# Power.net
KiCad netlist of a schematic drawn in Altium Designer
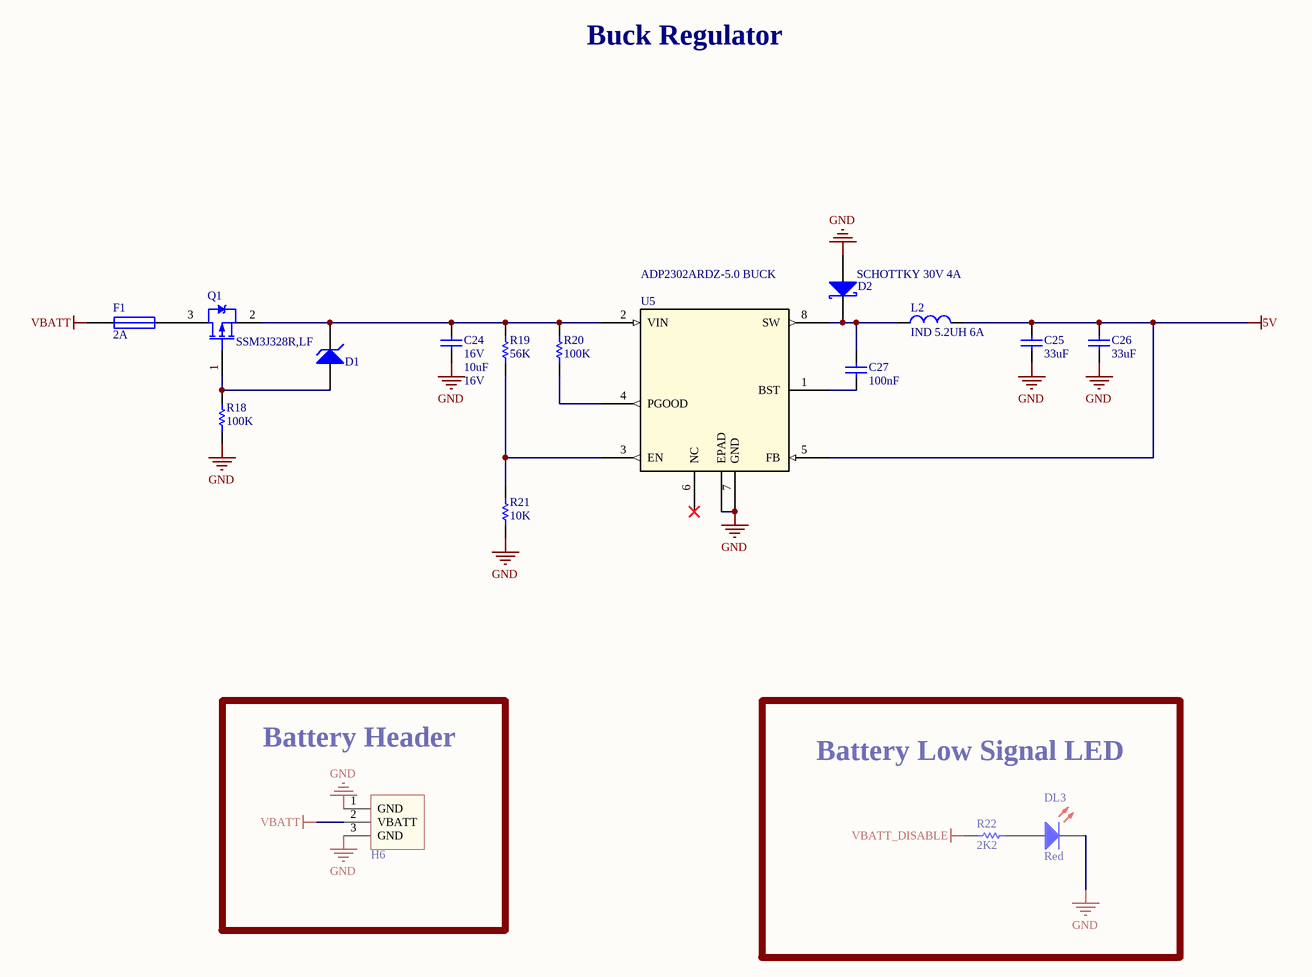
[diagram p0: Power.SchDoc]

(export (version "E")
  (design (tool "Eeschema 10.0.6"))
  (components
    (comp (ref "C24")
      (value "10uF")
      (footprint "CAPC2012L")
      (description "CAP CER 10uF X5R 16V 0805")
      (fields
        (field (name "MANUFACTURER") "Samsung Electro-Mechanics")
        (field (name "MANUFACTURER PART NUMBER") "CL21A106KOQNNWE")
        (field (name "VOLTAGE - RATED") "16V")
        (field (name "MAX VOLTAGE") "16V")
      )
      (libsource (lib "ENCE461AD19_19V2") (part "CC_10uF_16V_0805"))
    )
    (comp (ref "C25")
      (value "33uF")
      (footprint "CAPC2012L")
      (description "CAP CER 33uF X5R 6V3 0805")
      (fields
        (field (name "MANUFACTURER") "TDK Corporation")
        (field (name "MANUFACTURER PART NUMBER") "C2012X5R0J336M125AC")
      )
      (libsource (lib "ENCE461AD19_19V2") (part "CC_33uF_6V3_0805"))
    )
    (comp (ref "C26")
      (value "33uF")
      (footprint "CAPC2012L")
      (description "CAP CER 33uF X5R 6V3 0805")
      (fields
        (field (name "MANUFACTURER") "TDK Corporation")
        (field (name "MANUFACTURER PART NUMBER") "C2012X5R0J336M125AC")
      )
      (libsource (lib "ENCE461AD19_19V2") (part "CC_33uF_6V3_0805"))
    )
    (comp (ref "C27")
      (value "100nF")
      (footprint "CAPC1608L")
      (description "CAP CER 100nF X7R +-10% 50V 0603")
      (libsource (lib "ECE AD19Components_19V1") (part "CC_100nF_0603"))
    )
    (comp (ref "D1")
      (value "DIODE ZENER 5.6V")
      (footprint "DO-214AA_SCL")
      (description "DIODE ZENER 5.6V 5W DO214AA")
      (fields
        (field (name "MANUFACTURER") "Micro Commercial Co")
        (field (name "MANUFACTURER PART NUMBER") "SMBJ5339B-TP")
      )
      (libsource (lib "ENCE461AD19_19V2") (part "SMBJ5339B-TP"))
    )
    (comp (ref "D2")
      (value "SCHOTTKY 30V 4A")
      (footprint "SMC")
      (description "DIODE SCHOTTKY 30V 4A SMC")
      (fields
        (field (name "MANUFACTURER") "ON Semiconductor")
        (field (name "MANUFACTURER PART NUMBER") "MBRS330T3G")
      )
      (libsource (lib "ENCE461AD19_19V2") (part "MBRS330T3G"))
    )
    (comp (ref "DL3")
      (value "Red")
      (footprint "WL-SMCW0603")
      (description "LED Red 250mcd 0603 SMD")
      (fields
        (field (name "MANUFACTURER") "WURTH ELEKTRONIK")
        (field (name "MANUFACTURER PART NUMBER") "150060RS75000")
        (field (name "LED COLOUR") "Red")
      )
      (libsource (lib "ECE AD19Components_19V1") (part "DL_150060RS75000"))
    )
    (comp (ref "F1")
      (value "2A")
      (footprint "RESC3216N")
      (description "Fuse 2.0A Very Fast Acting 1206 SMD")
      (fields
        (field (name "MANUFACTURER") "MULTICOMP")
        (field (name "MANUFACTURER PART NUMBER") "MC12CF 002")
      )
      (libsource (lib "ECE AD19Components_19V1") (part "FS_Fuse_2.0A"))
    )
    (comp (ref "H6")
      (value "Battery_HEADER_3pin")
      (footprint "BATT_HEADER_3POS")
      (description "3Pin Header 2.54mm spacing")
      (libsource (lib "ENCE461AD19_19V2") (part "Battery_HEADER_3pin"))
    )
    (comp (ref "L2")
      (value "IND 5.2UH 6A")
      (footprint "INDUCTOR5u2")
      (description "FIXED IND 5.2UH 6A 22 MOHM SMD")
      (fields
        (field (name "MANUFACTURER") "Sumida America Components Inc.")
        (field (name "MANUFACTURER PART NUMBER") "CDRH104RNP-5R2NC")
      )
      (libsource (lib "ENCE461AD19_19V2") (part "CDRH104RNP-5R2NC"))
    )
    (comp (ref "Q1")
      (value "SSM3J328R,LF")
      (footprint "SOT23_L")
      (description "MOSFET P-CH 20V 6A SOT23-3")
      (fields
        (field (name "MANUFACTURER") "Toshiba")
        (field (name "MANUFACTURER PART NUMBER") "SSM3J328R,LF")
      )
      (libsource (lib "ECE AD19Components_19V1") (part "TM_SSM3J328R"))
    )
    (comp (ref "R18")
      (value "100K")
      (footprint "RESC1608L")
      (description "RES 100K OHM 1/10W 5% 0603 SMD")
      (libsource (lib "ECE AD19Components_19V1") (part "RS_100K"))
    )
    (comp (ref "R19")
      (value "56K")
      (footprint "RESC1608L")
      (description "RES 56.0K OHM 1/10W 5% 0603 SMD")
      (libsource (lib "ECE AD19Components_19V1") (part "RS_56K"))
    )
    (comp (ref "R20")
      (value "100K")
      (footprint "RESC1608L")
      (description "RES 100K OHM 1/10W 5% 0603 SMD")
      (libsource (lib "ECE AD19Components_19V1") (part "RS_100K"))
    )
    (comp (ref "R21")
      (value "10K")
      (footprint "RESC1608L")
      (description "RES 10.0K OHM 1/10W 5% 0603 SMD")
      (libsource (lib "ECE AD19Components_19V1") (part "RS_10K"))
    )
    (comp (ref "R22")
      (value "2K2")
      (footprint "RESC1608L")
      (description "RES 2.2K OHM 1/10W 5% 0603 SMD")
      (libsource (lib "ECE AD19Components_19V1") (part "RS_2K2"))
    )
    (comp (ref "U5")
      (value "ADP2302ARDZ-5.0 BUCK")
      (footprint "RD_8_1")
      (description "IC REG BUCK 5V 2A 8SOIC")
      (fields (field (name "MANUFACTURER_PART_NUMBER") "ADP2302ARDZ-5.0-R7"))
      (libsource (lib "ENCE461AD19_19V2") (part "ADP2302ARDZ-5.0-R7"))
    )
  )
  (nets
    (net (code "1") (name "5V") (class "Default")
      (node (ref "C25") (pin "2") (pinfunction "2_2") (pintype "passive"))
      (node (ref "C26") (pin "2") (pinfunction "2_2") (pintype "passive"))
      (node (ref "L2") (pin "2") (pintype "passive"))
      (node (ref "U5") (pin "5") (pinfunction "FB_5") (pintype "input"))
    )
    (net (code "2") (name "GND") (class "Default")
      (node (ref "C24") (pin "1") (pinfunction "1_1") (pintype "passive"))
      (node (ref "C25") (pin "1") (pinfunction "1_1") (pintype "passive"))
      (node (ref "C26") (pin "1") (pinfunction "1_1") (pintype "passive"))
      (node (ref "D2") (pin "1") (pinfunction "A_1") (pintype "passive"))
      (node (ref "DL3") (pin "1") (pinfunction "K_1") (pintype "passive"))
      (node (ref "H6") (pin "1") (pinfunction "GND_1") (pintype "passive"))
      (node (ref "H6") (pin "3") (pinfunction "GND_3") (pintype "passive"))
      (node (ref "R18") (pin "1") (pinfunction "1_1") (pintype "passive"))
      (node (ref "R21") (pin "1") (pinfunction "1_1") (pintype "passive"))
      (node (ref "U5") (pin "7") (pinfunction "GND_7") (pintype "power_in"))
      (node (ref "U5") (pin "EPAD") (pinfunction "EPAD_EPAD") (pintype "passive"))
    )
    (net (code "3") (name "Net-(D1-A)") (class "Default")
      (node (ref "D1") (pin "2") (pinfunction "A_2") (pintype "passive"))
      (node (ref "Q1") (pin "1") (pinfunction "1_1") (pintype "passive"))
      (node (ref "R18") (pin "2") (pinfunction "2_2") (pintype "passive"))
    )
    (net (code "4") (name "Net-(D1-K)") (class "Default")
      (node (ref "C24") (pin "2") (pinfunction "2_2") (pintype "passive"))
      (node (ref "D1") (pin "1") (pinfunction "K_1") (pintype "passive"))
      (node (ref "Q1") (pin "2") (pinfunction "2_2") (pintype "passive"))
      (node (ref "R19") (pin "2") (pinfunction "2_2") (pintype "passive"))
      (node (ref "R20") (pin "2") (pinfunction "2_2") (pintype "passive"))
      (node (ref "U5") (pin "2") (pinfunction "VIN_2") (pintype "input"))
    )
    (net (code "5") (name "Net-(D2-K)") (class "Default")
      (node (ref "C27") (pin "2") (pinfunction "2_2") (pintype "passive"))
      (node (ref "D2") (pin "2") (pinfunction "K_2") (pintype "passive"))
      (node (ref "L2") (pin "1") (pintype "passive"))
      (node (ref "U5") (pin "8") (pinfunction "SW_8") (pintype "output"))
    )
    (net (code "6") (name "Net-(DL3-A)") (class "Default")
      (node (ref "DL3") (pin "2") (pinfunction "A_2") (pintype "passive"))
      (node (ref "R22") (pin "2") (pinfunction "2_2") (pintype "passive"))
    )
    (net (code "7") (name "Net-(F1-Pad1)") (class "Default")
      (node (ref "F1") (pin "1") (pinfunction "1_1") (pintype "passive"))
      (node (ref "Q1") (pin "3") (pinfunction "3_3") (pintype "passive"))
    )
    (net (code "8") (name "Net-(U5-BST)") (class "Default")
      (node (ref "C27") (pin "1") (pinfunction "1_1") (pintype "passive"))
      (node (ref "U5") (pin "1") (pinfunction "BST_1") (pintype "passive"))
    )
    (net (code "9") (name "Net-(U5-EN)") (class "Default")
      (node (ref "R19") (pin "1") (pinfunction "1_1") (pintype "passive"))
      (node (ref "R21") (pin "2") (pinfunction "2_2") (pintype "passive"))
      (node (ref "U5") (pin "3") (pinfunction "EN_3") (pintype "output"))
    )
    (net (code "10") (name "Net-(U5-PGOOD)") (class "Default")
      (node (ref "R20") (pin "1") (pinfunction "1_1") (pintype "passive"))
      (node (ref "U5") (pin "4") (pinfunction "PGOOD_4") (pintype "output"))
    )
    (net (code "11") (name "VBATT") (class "Default")
      (node (ref "F1") (pin "2") (pinfunction "2_2") (pintype "passive"))
      (node (ref "H6") (pin "2") (pinfunction "VBATT_2") (pintype "passive"))
    )
    (net (code "12") (name "VBATT_DISABLE") (class "Default")
      (node (ref "R22") (pin "1") (pinfunction "1_1") (pintype "passive"))
    )
    (net (code "13") (name "unconnected-(U5-NC-Pad6)") (class "Default")
      (node (ref "U5") (pin "6") (pinfunction "NC_6") (pintype "passive+no_connect"))
    )
  )
)
